# DM3390_EEPROM.net
KiCad netlist of a schematic drawn in Altium Designer
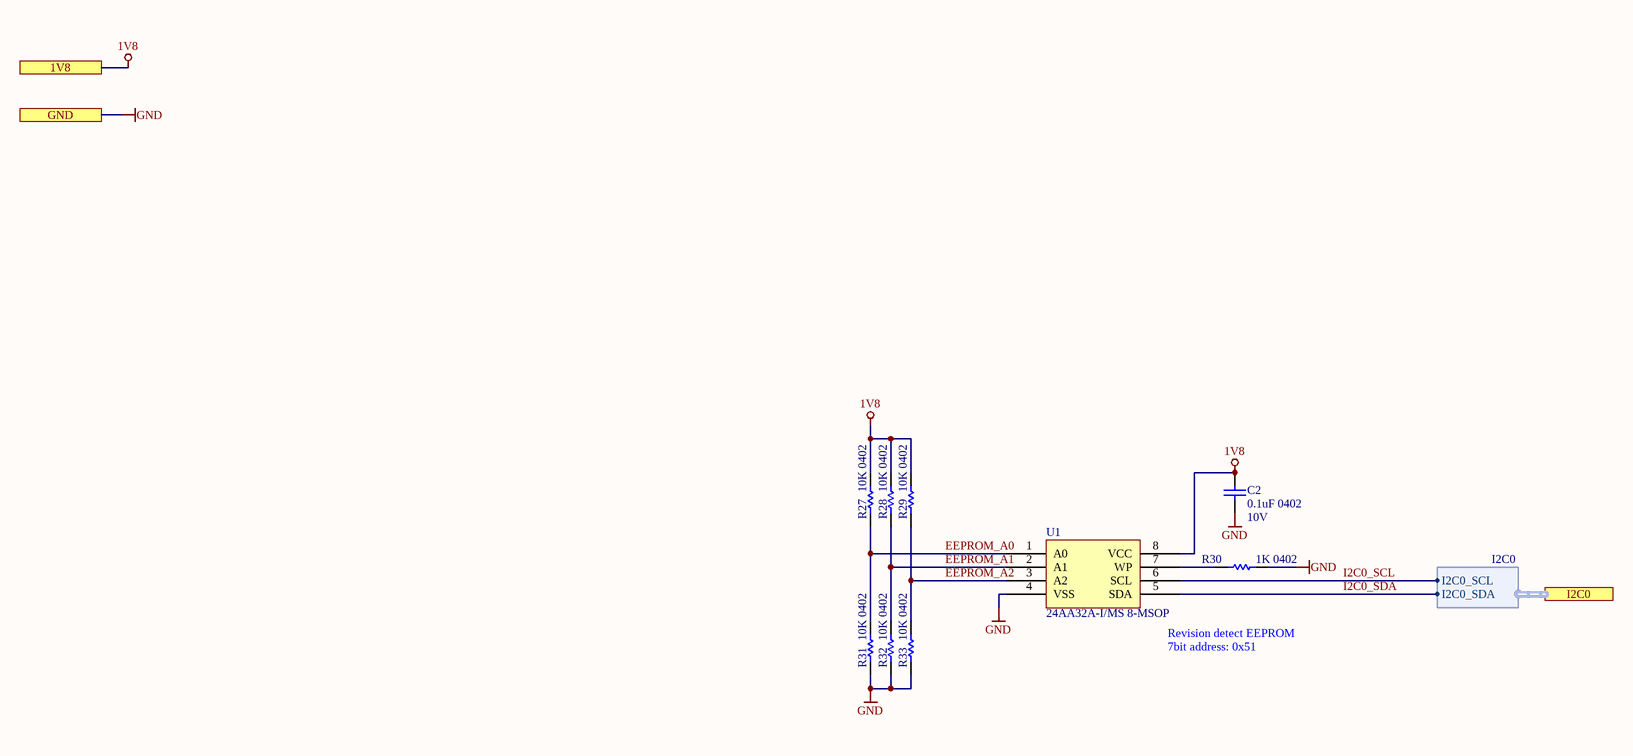
[diagram p0: DM3390_EEPROM.SchDoc]

(export (version "E")
  (design (tool "Eeschema 10.0.6"))
  (components
    (comp (ref "C2")
      (value "0.1uF 0402")
      (footprint "CAP_Altium_Vault_Generic:CAPC0402(1005)70_L")
      (description "CAP CER 0.1UF 10V X7R 0402 5%")
      (fields (field (name "TOLERANCE") "5%") (field (name "VOLTAGE RATING") "10V"))
      (libsource (lib "LuxonisMaster") (part "GRM155R71A104JA01D"))
    )
    (comp (ref "R27")
      (value "10K 0402")
      (footprint "RES_Altium_Vault_Generic:RESC0402(1005)_L")
      (fields (field (name "TOLERANCE") "1%"))
      (libsource (lib "LuxonisMaster") (part "RC0402FR-1310KL"))
    )
    (comp (ref "R28")
      (value "10K 0402")
      (footprint "RES_Altium_Vault_Generic:RESC0402(1005)_L")
      (fields (field (name "TOLERANCE") "1%"))
      (libsource (lib "LuxonisMaster") (part "RC0402FR-1310KL"))
    )
    (comp (ref "R29")
      (value "10K 0402")
      (footprint "RES_Altium_Vault_Generic:RESC0402(1005)_L")
      (fields (field (name "TOLERANCE") "1%"))
      (libsource (lib "LuxonisMaster") (part "RC0402FR-1310KL"))
    )
    (comp (ref "R30")
      (value "1K 0402")
      (footprint "RES_Altium_Vault_Generic:RESC0402(1005)_L")
      (description "RES SMD 1K OHM 1% 1/16W 0402")
      (fields (field (name "TOLERANCE") "1%"))
      (libsource (lib "LuxonisMaster") (part "RC0402FR-071KL"))
    )
    (comp (ref "R31")
      (value "10K 0402")
      (footprint "RES_Altium_Vault_Generic:RESC0402(1005)_L")
      (fields (field (name "TOLERANCE") "1%"))
      (libsource (lib "LuxonisMaster") (part "RC0402FR-1310KL"))
    )
    (comp (ref "R32")
      (value "10K 0402")
      (footprint "RES_Altium_Vault_Generic:RESC0402(1005)_L")
      (fields (field (name "TOLERANCE") "1%"))
      (libsource (lib "LuxonisMaster") (part "RC0402FR-1310KL"))
    )
    (comp (ref "R33")
      (value "10K 0402")
      (footprint "RES_Altium_Vault_Generic:RESC0402(1005)_L")
      (fields (field (name "TOLERANCE") "1%"))
      (libsource (lib "LuxonisMaster") (part "RC0402FR-1310KL"))
    )
    (comp (ref "U1")
      (value "24AA32A-I/MS 8-MSOP")
      (footprint "LuxonisMaster:24AA32A-I/MS")
      (description "IC EEPROM 32K I2C 400KHZ 8MSOP Memory IC 32Kb (4K x 8) I²C 400kHz 900ns 8-MSOP")
      (libsource (lib "LuxonisMaster") (part "24AA32A-I/MS"))
    )
  )
  (nets
    (net (code "2") (name "/EEPROM_A0") (class "Default")
      (node (ref "R27") (pin "1") (pinfunction "1_1") (pintype "passive"))
      (node (ref "R31") (pin "2") (pinfunction "2_2") (pintype "passive"))
      (node (ref "U1") (pin "1") (pinfunction "A0_1") (pintype "passive"))
    )
    (net (code "3") (name "/EEPROM_A1") (class "Default")
      (node (ref "R28") (pin "1") (pinfunction "1_1") (pintype "passive"))
      (node (ref "R32") (pin "2") (pinfunction "2_2") (pintype "passive"))
      (node (ref "U1") (pin "2") (pinfunction "A1_2") (pintype "passive"))
    )
    (net (code "4") (name "/EEPROM_A2") (class "Default")
      (node (ref "R29") (pin "1") (pinfunction "1_1") (pintype "passive"))
      (node (ref "R33") (pin "2") (pinfunction "2_2") (pintype "passive"))
      (node (ref "U1") (pin "3") (pinfunction "A2_3") (pintype "passive"))
    )
    (net (code "5") (name "/I2C0_SCL") (class "Default")
      (node (ref "U1") (pin "6") (pinfunction "SCL_6") (pintype "passive"))
    )
    (net (code "6") (name "/I2C0_SDA") (class "Default")
      (node (ref "U1") (pin "5") (pinfunction "SDA_5") (pintype "passive"))
    )
    (net (code "8") (name "1V8") (class "Default")
      (node (ref "C2") (pin "2") (pinfunction "2_2") (pintype "passive"))
      (node (ref "R27") (pin "2") (pinfunction "2_2") (pintype "passive"))
      (node (ref "R28") (pin "2") (pinfunction "2_2") (pintype "passive"))
      (node (ref "R29") (pin "2") (pinfunction "2_2") (pintype "passive"))
      (node (ref "U1") (pin "8") (pinfunction "VCC_8") (pintype "passive"))
    )
    (net (code "9") (name "GND") (class "Default")
      (node (ref "C2") (pin "1") (pinfunction "1_1") (pintype "passive"))
      (node (ref "R30") (pin "1") (pinfunction "1_1") (pintype "passive"))
      (node (ref "R31") (pin "1") (pinfunction "1_1") (pintype "passive"))
      (node (ref "R32") (pin "1") (pinfunction "1_1") (pintype "passive"))
      (node (ref "R33") (pin "1") (pinfunction "1_1") (pintype "passive"))
      (node (ref "U1") (pin "4") (pinfunction "VSS_4") (pintype "passive"))
    )
    (net (code "10") (name "Net-(U1-WP)") (class "Default")
      (node (ref "R30") (pin "2") (pinfunction "2_2") (pintype "passive"))
      (node (ref "U1") (pin "7") (pinfunction "WP_7") (pintype "passive"))
    )
  )
)
